# esquematico_proyecto.net
KiCad netlist of a schematic drawn in EAGLE
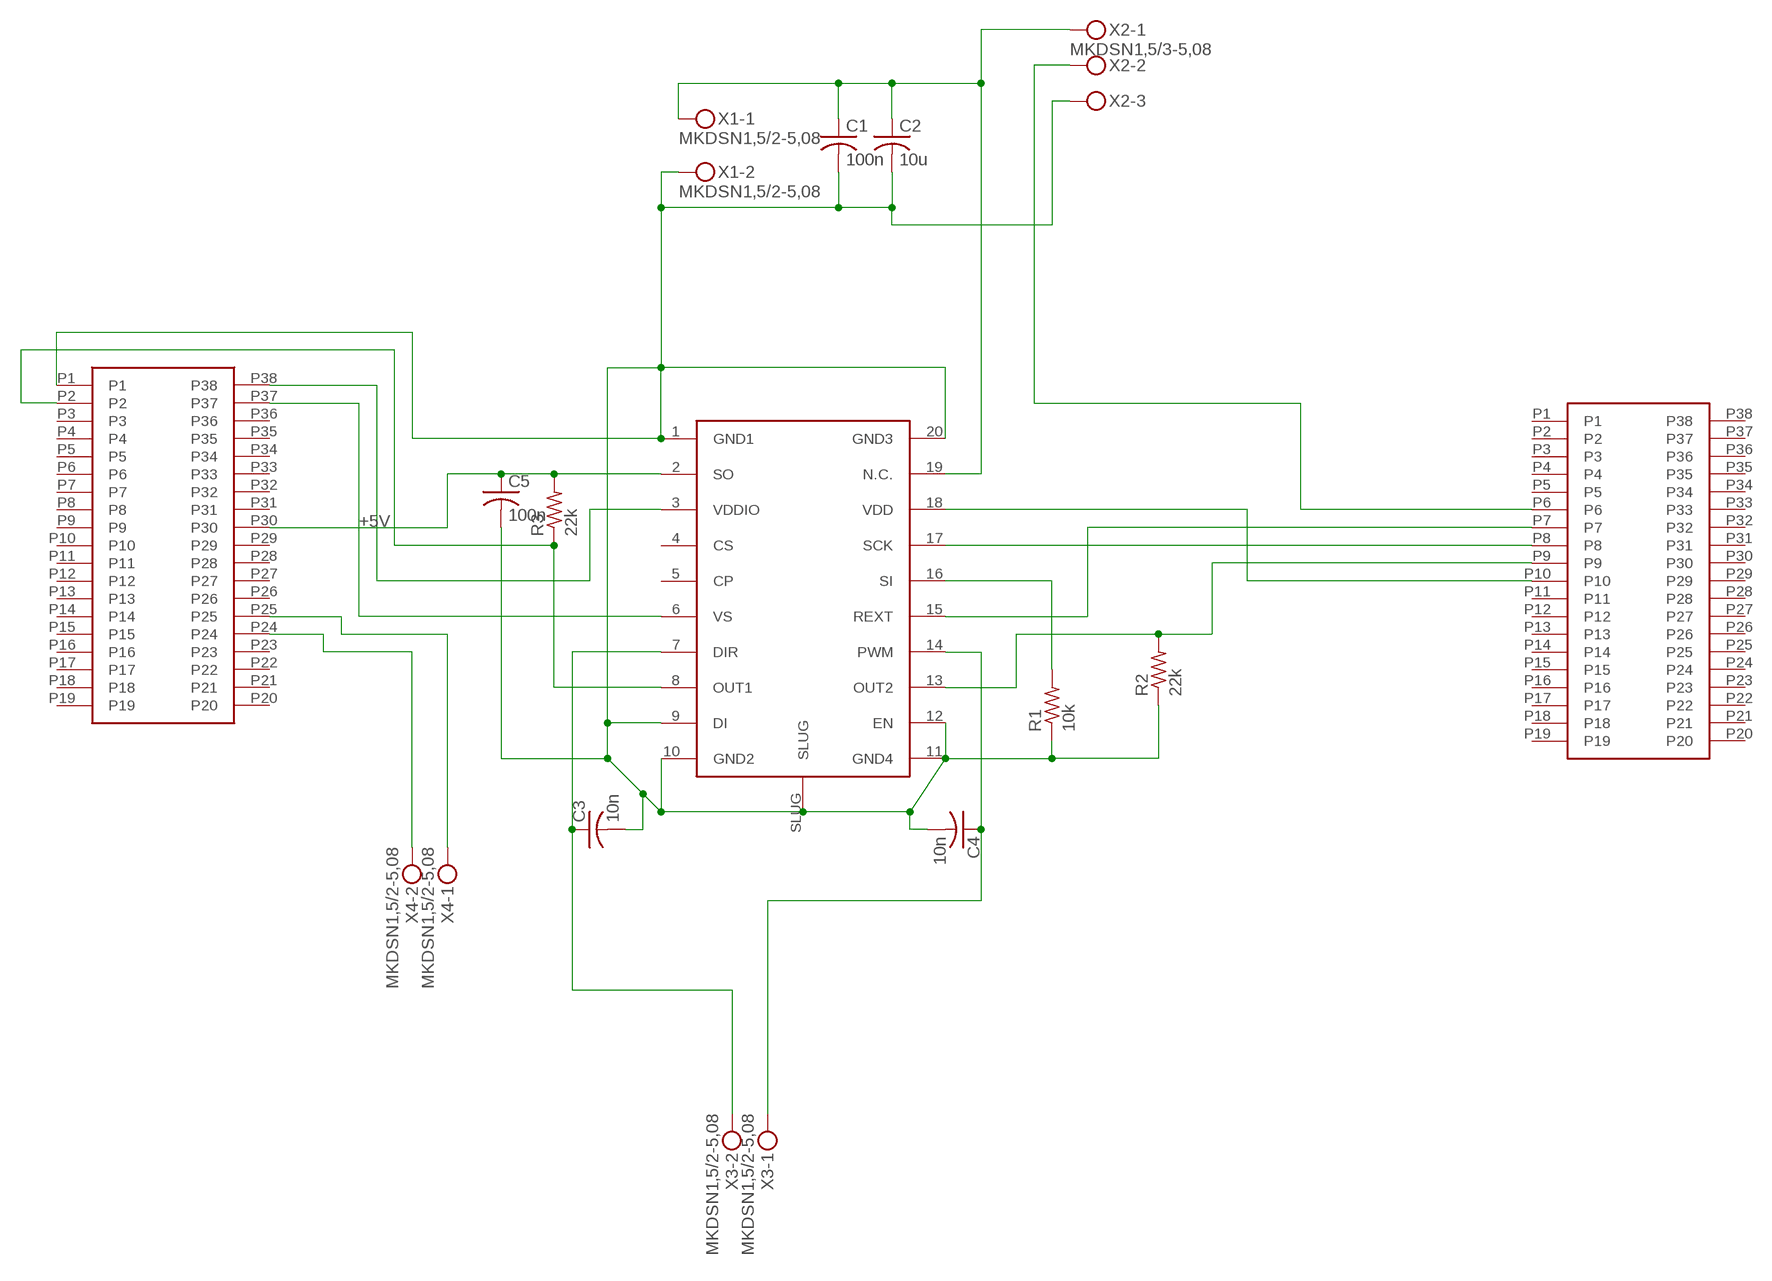
[diagram p0: schematic, sheet 1]

(export (version "E")
  (design (tool "Eeschema 10.0.6"))
  (components
    (comp (ref "C1")
      (value "100n")
      (footprint "eagle-import:C0603")
      (libsource (lib "eagle-import") (part "C-USC0603"))
    )
    (comp (ref "C2")
      (value "10u")
      (footprint "eagle-import:C0805")
      (libsource (lib "eagle-import") (part "C-USC0805"))
    )
    (comp (ref "C3")
      (value "10n")
      (footprint "eagle-import:C0201")
      (libsource (lib "eagle-import") (part "rcl_334_C-USC0201"))
    )
    (comp (ref "C4")
      (value "10n")
      (footprint "eagle-import:C0201")
      (libsource (lib "eagle-import") (part "rcl_334_C-USC0201"))
    )
    (comp (ref "C5")
      (value "100n")
      (footprint "eagle-import:C0603")
      (libsource (lib "eagle-import") (part "C-USC0603"))
    )
    (comp (ref "R1")
      (value "10k")
      (footprint "eagle-import:R0805")
      (libsource (lib "eagle-import") (part "R-US_R0805"))
    )
    (comp (ref "R2")
      (value "22k")
      (footprint "eagle-import:R0805")
      (libsource (lib "eagle-import") (part "R-US_R0805"))
    )
    (comp (ref "R3")
      (value "22k")
      (footprint "eagle-import:R0805")
      (libsource (lib "eagle-import") (part "R-US_R0805"))
    )
    (comp (ref "U$1")
      (value "L9958L9958")
      (footprint "eagle-import:L9958")
      (libsource (lib "eagle-import") (part "L9958L9958"))
    )
    (comp (ref "U$2")
      (value "PINHEADER")
      (footprint "eagle-import:PINHEADER")
      (libsource (lib "eagle-import") (part "PINHEADER"))
    )
    (comp (ref "U$3")
      (value "PINHEADER")
      (footprint "eagle-import:PINHEADER")
      (libsource (lib "eagle-import") (part "PINHEADER"))
    )
    (comp (ref "X1")
      (value "MKDSN1,5/2-5,08")
      (footprint "eagle-import:MKDSN1,5_2-5,08")
      (libsource (lib "eagle-import") (part "MKDSN1,5/2-5,08"))
    )
    (comp (ref "X2")
      (value "MKDSN1,5/3-5,08")
      (footprint "eagle-import:MKDSN1,5_3-5,08")
      (libsource (lib "eagle-import") (part "MKDSN1,5/3-5,08"))
    )
    (comp (ref "X3")
      (value "MKDSN1,5/2-5,08")
      (footprint "eagle-import:MKDSN1,5_2-5,08")
      (libsource (lib "eagle-import") (part "con-phoenix-508_176_MKDSN1,5/2-5,08"))
    )
    (comp (ref "X4")
      (value "MKDSN1,5/2-5,08")
      (footprint "eagle-import:MKDSN1,5_2-5,08")
      (libsource (lib "eagle-import") (part "con-phoenix-508_176_MKDSN1,5/2-5,08"))
    )
  )
  (nets
    (net (code "1") (name "/+5V") (class "Default")
      (node (ref "C5") (pin "1") (pinfunction "1_1") (pintype "passive"))
      (node (ref "R3") (pin "2") (pinfunction "2_2") (pintype "passive"))
      (node (ref "U$1") (pin "2") (pinfunction "SO_2") (pintype "bidirectional"))
      (node (ref "U$2") (pin "P30") (pinfunction "P30_P30") (pintype "bidirectional"))
    )
    (net (code "2") (name "Net-(U$1-DI)") (class "Default")
      (node (ref "C1") (pin "2") (pinfunction "2_2") (pintype "passive"))
      (node (ref "C2") (pin "2") (pinfunction "2_2") (pintype "passive"))
      (node (ref "C3") (pin "2") (pinfunction "2_2") (pintype "passive"))
      (node (ref "C4") (pin "2") (pinfunction "2_2") (pintype "passive"))
      (node (ref "C5") (pin "2") (pinfunction "2_2") (pintype "passive"))
      (node (ref "R1") (pin "1") (pinfunction "1_1") (pintype "passive"))
      (node (ref "R2") (pin "1") (pinfunction "1_1") (pintype "passive"))
      (node (ref "U$1") (pin "1") (pinfunction "GND1_1") (pintype "bidirectional"))
      (node (ref "U$1") (pin "10") (pinfunction "GND2_10") (pintype "bidirectional"))
      (node (ref "U$1") (pin "11") (pinfunction "GND4_11") (pintype "bidirectional"))
      (node (ref "U$1") (pin "12") (pinfunction "EN_12") (pintype "bidirectional"))
      (node (ref "U$1") (pin "20") (pinfunction "GND3_20") (pintype "bidirectional"))
      (node (ref "U$1") (pin "9") (pinfunction "DI_9") (pintype "bidirectional"))
      (node (ref "U$1") (pin "SLUG") (pinfunction "SLUG_SLUG") (pintype "bidirectional"))
      (node (ref "U$2") (pin "P1") (pinfunction "P1_P1") (pintype "bidirectional"))
      (node (ref "X1") (pin "2") (pinfunction "KL_2") (pintype "passive"))
      (node (ref "X2") (pin "3") (pinfunction "KL_3") (pintype "passive"))
    )
    (net (code "3") (name "Net-(U$1-DIR)") (class "Default")
      (node (ref "C3") (pin "1") (pinfunction "1_1") (pintype "passive"))
      (node (ref "U$1") (pin "7") (pinfunction "DIR_7") (pintype "bidirectional"))
      (node (ref "X3") (pin "2") (pinfunction "KL_2") (pintype "passive"))
    )
    (net (code "4") (name "Net-(U$1-N.C.)") (class "Default")
      (node (ref "C1") (pin "1") (pinfunction "1_1") (pintype "passive"))
      (node (ref "C2") (pin "1") (pinfunction "1_1") (pintype "passive"))
      (node (ref "U$1") (pin "19") (pinfunction "N.C._19") (pintype "bidirectional"))
      (node (ref "X1") (pin "1") (pinfunction "KL_1") (pintype "passive"))
      (node (ref "X2") (pin "1") (pinfunction "KL_1") (pintype "passive"))
    )
    (net (code "5") (name "Net-(U$1-OUT1)") (class "Default")
      (node (ref "R3") (pin "1") (pinfunction "1_1") (pintype "passive"))
      (node (ref "U$1") (pin "8") (pinfunction "OUT1_8") (pintype "bidirectional"))
      (node (ref "U$2") (pin "P2") (pinfunction "P2_P2") (pintype "bidirectional"))
    )
    (net (code "6") (name "Net-(U$1-OUT2)") (class "Default")
      (node (ref "R2") (pin "2") (pinfunction "2_2") (pintype "passive"))
      (node (ref "U$1") (pin "13") (pinfunction "OUT2_13") (pintype "bidirectional"))
      (node (ref "U$3") (pin "P9") (pinfunction "P9_P9") (pintype "bidirectional"))
    )
    (net (code "7") (name "Net-(U$1-PWM)") (class "Default")
      (node (ref "C4") (pin "1") (pinfunction "1_1") (pintype "passive"))
      (node (ref "U$1") (pin "14") (pinfunction "PWM_14") (pintype "bidirectional"))
      (node (ref "X3") (pin "1") (pinfunction "KL_1") (pintype "passive"))
    )
    (net (code "8") (name "Net-(U$1-REXT)") (class "Default")
      (node (ref "U$1") (pin "15") (pinfunction "REXT_15") (pintype "bidirectional"))
      (node (ref "U$3") (pin "P7") (pinfunction "P7_P7") (pintype "bidirectional"))
    )
    (net (code "9") (name "Net-(U$1-SCK)") (class "Default")
      (node (ref "U$1") (pin "17") (pinfunction "SCK_17") (pintype "bidirectional"))
      (node (ref "U$3") (pin "P8") (pinfunction "P8_P8") (pintype "bidirectional"))
    )
    (net (code "10") (name "Net-(U$1-SI)") (class "Default")
      (node (ref "R1") (pin "2") (pinfunction "2_2") (pintype "passive"))
      (node (ref "U$1") (pin "16") (pinfunction "SI_16") (pintype "bidirectional"))
    )
    (net (code "11") (name "Net-(U$1-VDD)") (class "Default")
      (node (ref "U$1") (pin "18") (pinfunction "VDD_18") (pintype "bidirectional"))
      (node (ref "U$3") (pin "P10") (pinfunction "P10_P10") (pintype "bidirectional"))
    )
    (net (code "12") (name "Net-(U$1-VDDIO)") (class "Default")
      (node (ref "U$1") (pin "3") (pinfunction "VDDIO_3") (pintype "bidirectional"))
      (node (ref "U$2") (pin "P38") (pinfunction "P38_P38") (pintype "bidirectional"))
    )
    (net (code "13") (name "Net-(U$1-VS)") (class "Default")
      (node (ref "U$1") (pin "6") (pinfunction "VS_6") (pintype "bidirectional"))
      (node (ref "U$2") (pin "P37") (pinfunction "P37_P37") (pintype "bidirectional"))
    )
    (net (code "14") (name "Net-(X2B-KL)") (class "Default")
      (node (ref "U$3") (pin "P6") (pinfunction "P6_P6") (pintype "bidirectional"))
      (node (ref "X2") (pin "2") (pinfunction "KL_2") (pintype "passive"))
    )
    (net (code "15") (name "Net-(X4A-KL)") (class "Default")
      (node (ref "U$2") (pin "P25") (pinfunction "P25_P25") (pintype "bidirectional"))
      (node (ref "X4") (pin "1") (pinfunction "KL_1") (pintype "passive"))
    )
    (net (code "16") (name "Net-(X4B-KL)") (class "Default")
      (node (ref "U$2") (pin "P24") (pinfunction "P24_P24") (pintype "bidirectional"))
      (node (ref "X4") (pin "2") (pinfunction "KL_2") (pintype "passive"))
    )
    (net (code "17") (name "unconnected-(U$1-CP-Pad5)") (class "Default")
      (node (ref "U$1") (pin "5") (pinfunction "CP_5") (pintype "bidirectional"))
    )
    (net (code "18") (name "unconnected-(U$1-CS-Pad4)") (class "Default")
      (node (ref "U$1") (pin "4") (pinfunction "CS_4") (pintype "bidirectional"))
    )
    (net (code "19") (name "unconnected-(U$2-PadP3)") (class "Default")
      (node (ref "U$2") (pin "P3") (pinfunction "P3_P3") (pintype "bidirectional"))
    )
    (net (code "20") (name "unconnected-(U$2-PadP4)") (class "Default")
      (node (ref "U$2") (pin "P4") (pinfunction "P4_P4") (pintype "bidirectional"))
    )
    (net (code "21") (name "unconnected-(U$2-PadP5)") (class "Default")
      (node (ref "U$2") (pin "P5") (pinfunction "P5_P5") (pintype "bidirectional"))
    )
    (net (code "22") (name "unconnected-(U$2-PadP6)") (class "Default")
      (node (ref "U$2") (pin "P6") (pinfunction "P6_P6") (pintype "bidirectional"))
    )
    (net (code "23") (name "unconnected-(U$2-PadP7)") (class "Default")
      (node (ref "U$2") (pin "P7") (pinfunction "P7_P7") (pintype "bidirectional"))
    )
    (net (code "24") (name "unconnected-(U$2-PadP8)") (class "Default")
      (node (ref "U$2") (pin "P8") (pinfunction "P8_P8") (pintype "bidirectional"))
    )
    (net (code "25") (name "unconnected-(U$2-PadP9)") (class "Default")
      (node (ref "U$2") (pin "P9") (pinfunction "P9_P9") (pintype "bidirectional"))
    )
    (net (code "26") (name "unconnected-(U$2-PadP10)") (class "Default")
      (node (ref "U$2") (pin "P10") (pinfunction "P10_P10") (pintype "bidirectional"))
    )
    (net (code "27") (name "unconnected-(U$2-PadP11)") (class "Default")
      (node (ref "U$2") (pin "P11") (pinfunction "P11_P11") (pintype "bidirectional"))
    )
    (net (code "28") (name "unconnected-(U$2-PadP12)") (class "Default")
      (node (ref "U$2") (pin "P12") (pinfunction "P12_P12") (pintype "bidirectional"))
    )
    (net (code "29") (name "unconnected-(U$2-PadP13)") (class "Default")
      (node (ref "U$2") (pin "P13") (pinfunction "P13_P13") (pintype "bidirectional"))
    )
    (net (code "30") (name "unconnected-(U$2-PadP14)") (class "Default")
      (node (ref "U$2") (pin "P14") (pinfunction "P14_P14") (pintype "bidirectional"))
    )
    (net (code "31") (name "unconnected-(U$2-PadP15)") (class "Default")
      (node (ref "U$2") (pin "P15") (pinfunction "P15_P15") (pintype "bidirectional"))
    )
    (net (code "32") (name "unconnected-(U$2-PadP16)") (class "Default")
      (node (ref "U$2") (pin "P16") (pinfunction "P16_P16") (pintype "bidirectional"))
    )
    (net (code "33") (name "unconnected-(U$2-PadP17)") (class "Default")
      (node (ref "U$2") (pin "P17") (pinfunction "P17_P17") (pintype "bidirectional"))
    )
    (net (code "34") (name "unconnected-(U$2-PadP18)") (class "Default")
      (node (ref "U$2") (pin "P18") (pinfunction "P18_P18") (pintype "bidirectional"))
    )
    (net (code "35") (name "unconnected-(U$2-PadP19)") (class "Default")
      (node (ref "U$2") (pin "P19") (pinfunction "P19_P19") (pintype "bidirectional"))
    )
    (net (code "36") (name "unconnected-(U$2-PadP20)") (class "Default")
      (node (ref "U$2") (pin "P20") (pinfunction "P20_P20") (pintype "bidirectional"))
    )
    (net (code "37") (name "unconnected-(U$2-PadP21)") (class "Default")
      (node (ref "U$2") (pin "P21") (pinfunction "P21_P21") (pintype "bidirectional"))
    )
    (net (code "38") (name "unconnected-(U$2-PadP22)") (class "Default")
      (node (ref "U$2") (pin "P22") (pinfunction "P22_P22") (pintype "bidirectional"))
    )
    (net (code "39") (name "unconnected-(U$2-PadP23)") (class "Default")
      (node (ref "U$2") (pin "P23") (pinfunction "P23_P23") (pintype "bidirectional"))
    )
    (net (code "40") (name "unconnected-(U$2-PadP26)") (class "Default")
      (node (ref "U$2") (pin "P26") (pinfunction "P26_P26") (pintype "bidirectional"))
    )
    (net (code "41") (name "unconnected-(U$2-PadP27)") (class "Default")
      (node (ref "U$2") (pin "P27") (pinfunction "P27_P27") (pintype "bidirectional"))
    )
    (net (code "42") (name "unconnected-(U$2-PadP28)") (class "Default")
      (node (ref "U$2") (pin "P28") (pinfunction "P28_P28") (pintype "bidirectional"))
    )
    (net (code "43") (name "unconnected-(U$2-PadP29)") (class "Default")
      (node (ref "U$2") (pin "P29") (pinfunction "P29_P29") (pintype "bidirectional"))
    )
    (net (code "44") (name "unconnected-(U$2-PadP31)") (class "Default")
      (node (ref "U$2") (pin "P31") (pinfunction "P31_P31") (pintype "bidirectional"))
    )
    (net (code "45") (name "unconnected-(U$2-PadP32)") (class "Default")
      (node (ref "U$2") (pin "P32") (pinfunction "P32_P32") (pintype "bidirectional"))
    )
    (net (code "46") (name "unconnected-(U$2-PadP33)") (class "Default")
      (node (ref "U$2") (pin "P33") (pinfunction "P33_P33") (pintype "bidirectional"))
    )
    (net (code "47") (name "unconnected-(U$2-PadP34)") (class "Default")
      (node (ref "U$2") (pin "P34") (pinfunction "P34_P34") (pintype "bidirectional"))
    )
    (net (code "48") (name "unconnected-(U$2-PadP35)") (class "Default")
      (node (ref "U$2") (pin "P35") (pinfunction "P35_P35") (pintype "bidirectional"))
    )
    (net (code "49") (name "unconnected-(U$2-PadP36)") (class "Default")
      (node (ref "U$2") (pin "P36") (pinfunction "P36_P36") (pintype "bidirectional"))
    )
    (net (code "50") (name "unconnected-(U$3-PadP1)") (class "Default")
      (node (ref "U$3") (pin "P1") (pinfunction "P1_P1") (pintype "bidirectional"))
    )
    (net (code "51") (name "unconnected-(U$3-PadP2)") (class "Default")
      (node (ref "U$3") (pin "P2") (pinfunction "P2_P2") (pintype "bidirectional"))
    )
    (net (code "52") (name "unconnected-(U$3-PadP3)") (class "Default")
      (node (ref "U$3") (pin "P3") (pinfunction "P3_P3") (pintype "bidirectional"))
    )
    (net (code "53") (name "unconnected-(U$3-PadP4)") (class "Default")
      (node (ref "U$3") (pin "P4") (pinfunction "P4_P4") (pintype "bidirectional"))
    )
    (net (code "54") (name "unconnected-(U$3-PadP5)") (class "Default")
      (node (ref "U$3") (pin "P5") (pinfunction "P5_P5") (pintype "bidirectional"))
    )
    (net (code "55") (name "unconnected-(U$3-PadP11)") (class "Default")
      (node (ref "U$3") (pin "P11") (pinfunction "P11_P11") (pintype "bidirectional"))
    )
    (net (code "56") (name "unconnected-(U$3-PadP12)") (class "Default")
      (node (ref "U$3") (pin "P12") (pinfunction "P12_P12") (pintype "bidirectional"))
    )
    (net (code "57") (name "unconnected-(U$3-PadP13)") (class "Default")
      (node (ref "U$3") (pin "P13") (pinfunction "P13_P13") (pintype "bidirectional"))
    )
    (net (code "58") (name "unconnected-(U$3-PadP14)") (class "Default")
      (node (ref "U$3") (pin "P14") (pinfunction "P14_P14") (pintype "bidirectional"))
    )
    (net (code "59") (name "unconnected-(U$3-PadP15)") (class "Default")
      (node (ref "U$3") (pin "P15") (pinfunction "P15_P15") (pintype "bidirectional"))
    )
    (net (code "60") (name "unconnected-(U$3-PadP16)") (class "Default")
      (node (ref "U$3") (pin "P16") (pinfunction "P16_P16") (pintype "bidirectional"))
    )
    (net (code "61") (name "unconnected-(U$3-PadP17)") (class "Default")
      (node (ref "U$3") (pin "P17") (pinfunction "P17_P17") (pintype "bidirectional"))
    )
    (net (code "62") (name "unconnected-(U$3-PadP18)") (class "Default")
      (node (ref "U$3") (pin "P18") (pinfunction "P18_P18") (pintype "bidirectional"))
    )
    (net (code "63") (name "unconnected-(U$3-PadP19)") (class "Default")
      (node (ref "U$3") (pin "P19") (pinfunction "P19_P19") (pintype "bidirectional"))
    )
    (net (code "64") (name "unconnected-(U$3-PadP20)") (class "Default")
      (node (ref "U$3") (pin "P20") (pinfunction "P20_P20") (pintype "bidirectional"))
    )
    (net (code "65") (name "unconnected-(U$3-PadP21)") (class "Default")
      (node (ref "U$3") (pin "P21") (pinfunction "P21_P21") (pintype "bidirectional"))
    )
    (net (code "66") (name "unconnected-(U$3-PadP22)") (class "Default")
      (node (ref "U$3") (pin "P22") (pinfunction "P22_P22") (pintype "bidirectional"))
    )
    (net (code "67") (name "unconnected-(U$3-PadP23)") (class "Default")
      (node (ref "U$3") (pin "P23") (pinfunction "P23_P23") (pintype "bidirectional"))
    )
    (net (code "68") (name "unconnected-(U$3-PadP24)") (class "Default")
      (node (ref "U$3") (pin "P24") (pinfunction "P24_P24") (pintype "bidirectional"))
    )
    (net (code "69") (name "unconnected-(U$3-PadP25)") (class "Default")
      (node (ref "U$3") (pin "P25") (pinfunction "P25_P25") (pintype "bidirectional"))
    )
    (net (code "70") (name "unconnected-(U$3-PadP26)") (class "Default")
      (node (ref "U$3") (pin "P26") (pinfunction "P26_P26") (pintype "bidirectional"))
    )
    (net (code "71") (name "unconnected-(U$3-PadP27)") (class "Default")
      (node (ref "U$3") (pin "P27") (pinfunction "P27_P27") (pintype "bidirectional"))
    )
    (net (code "72") (name "unconnected-(U$3-PadP28)") (class "Default")
      (node (ref "U$3") (pin "P28") (pinfunction "P28_P28") (pintype "bidirectional"))
    )
    (net (code "73") (name "unconnected-(U$3-PadP29)") (class "Default")
      (node (ref "U$3") (pin "P29") (pinfunction "P29_P29") (pintype "bidirectional"))
    )
    (net (code "74") (name "unconnected-(U$3-PadP30)") (class "Default")
      (node (ref "U$3") (pin "P30") (pinfunction "P30_P30") (pintype "bidirectional"))
    )
    (net (code "75") (name "unconnected-(U$3-PadP31)") (class "Default")
      (node (ref "U$3") (pin "P31") (pinfunction "P31_P31") (pintype "bidirectional"))
    )
    (net (code "76") (name "unconnected-(U$3-PadP32)") (class "Default")
      (node (ref "U$3") (pin "P32") (pinfunction "P32_P32") (pintype "bidirectional"))
    )
    (net (code "77") (name "unconnected-(U$3-PadP33)") (class "Default")
      (node (ref "U$3") (pin "P33") (pinfunction "P33_P33") (pintype "bidirectional"))
    )
    (net (code "78") (name "unconnected-(U$3-PadP34)") (class "Default")
      (node (ref "U$3") (pin "P34") (pinfunction "P34_P34") (pintype "bidirectional"))
    )
    (net (code "79") (name "unconnected-(U$3-PadP35)") (class "Default")
      (node (ref "U$3") (pin "P35") (pinfunction "P35_P35") (pintype "bidirectional"))
    )
    (net (code "80") (name "unconnected-(U$3-PadP36)") (class "Default")
      (node (ref "U$3") (pin "P36") (pinfunction "P36_P36") (pintype "bidirectional"))
    )
    (net (code "81") (name "unconnected-(U$3-PadP37)") (class "Default")
      (node (ref "U$3") (pin "P37") (pinfunction "P37_P37") (pintype "bidirectional"))
    )
    (net (code "82") (name "unconnected-(U$3-PadP38)") (class "Default")
      (node (ref "U$3") (pin "P38") (pinfunction "P38_P38") (pintype "bidirectional"))
    )
  )
)
